# serial.net
KiCad netlist of a schematic drawn in Altium Designer
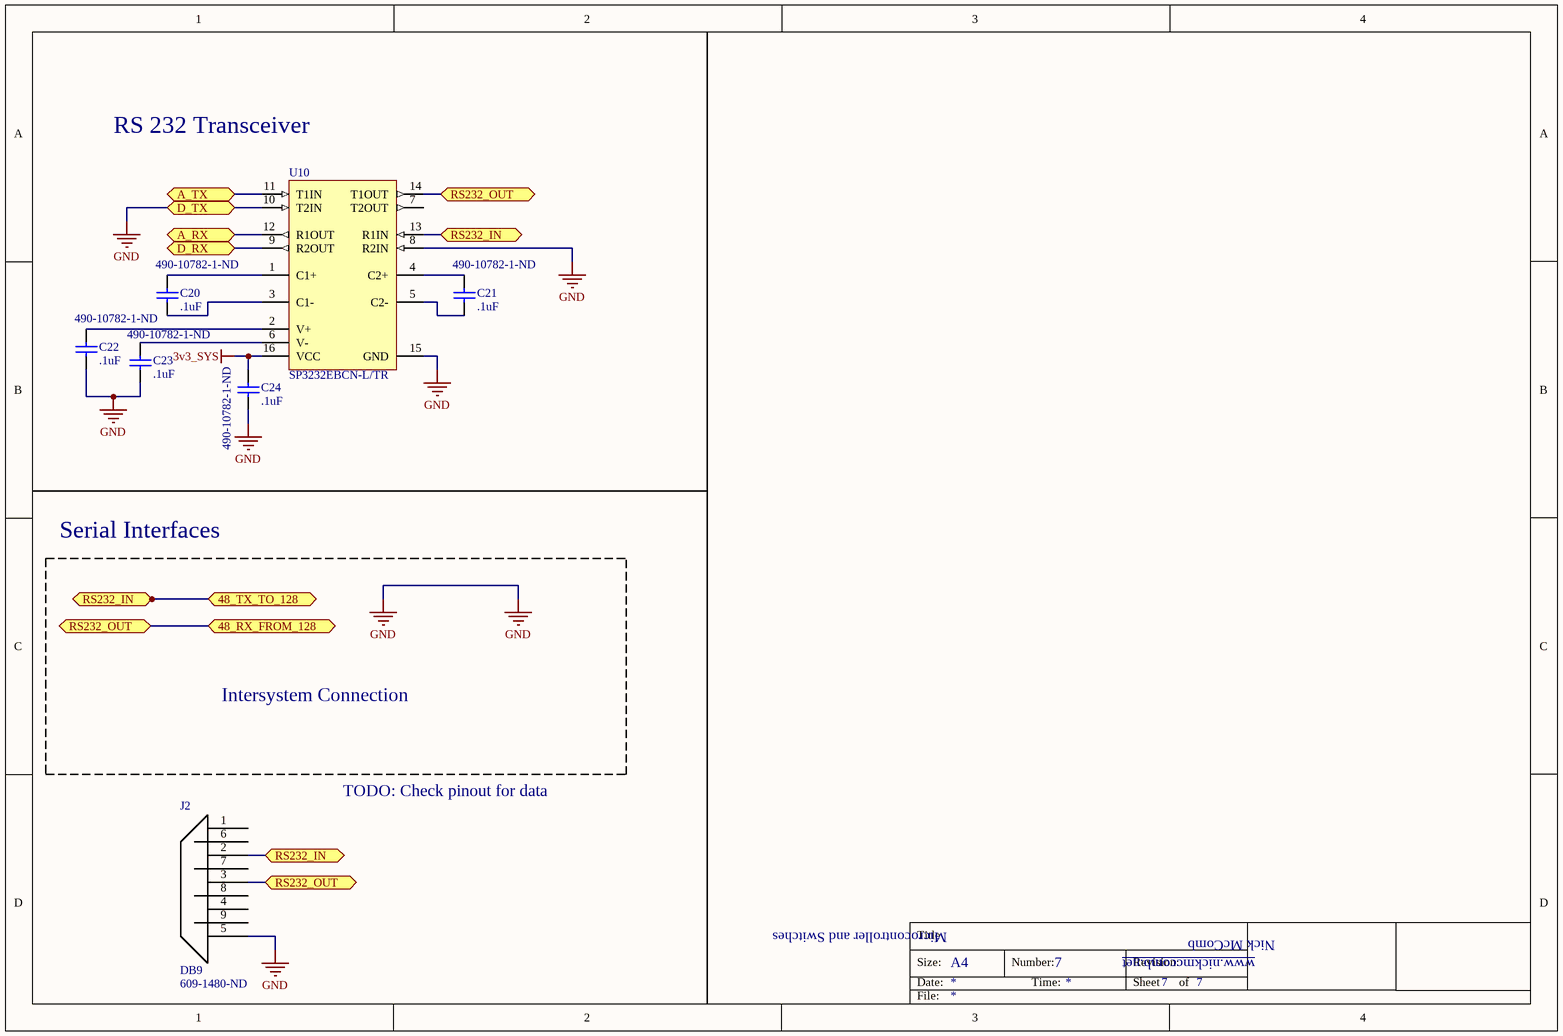
[diagram p0: serial.SchDoc]

(export (version "E")
  (design (tool "Eeschema 10.0.6"))
  (components
    (comp (ref "C20")
      (value ".1uF")
      (footprint "C0805")
      (description "Capacitor")
      (fields
        (field (name "SUPPLIER PART NUMBER 1") "490-10782-1-ND")
        (field (name "MANUFACTURER") "Murata Electronics North America")
        (field (name "MANUFACTURER PART NUMBER") "GRM21BR71H104JA01L")
        (field (name "PUBLISHER") "Altium Limited")
      )
      (libsource (lib "MultiAdapterLib") (part "Cap"))
    )
    (comp (ref "C21")
      (value ".1uF")
      (footprint "C0805")
      (description "Capacitor")
      (fields
        (field (name "SUPPLIER PART NUMBER 1") "490-10782-1-ND")
        (field (name "MANUFACTURER") "Murata Electronics North America")
        (field (name "MANUFACTURER PART NUMBER") "GRM21BR71H104JA01L")
        (field (name "PUBLISHER") "Altium Limited")
      )
      (libsource (lib "MultiAdapterLib") (part "Cap"))
    )
    (comp (ref "C22")
      (value ".1uF")
      (footprint "C0805")
      (description "Capacitor")
      (fields
        (field (name "SUPPLIER PART NUMBER 1") "490-10782-1-ND")
        (field (name "MANUFACTURER") "Murata Electronics North America")
        (field (name "MANUFACTURER PART NUMBER") "GRM21BR71H104JA01L")
        (field (name "PUBLISHER") "Altium Limited")
      )
      (libsource (lib "MultiAdapterLib") (part "Cap"))
    )
    (comp (ref "C23")
      (value ".1uF")
      (footprint "C0805")
      (description "Capacitor")
      (fields
        (field (name "SUPPLIER PART NUMBER 1") "490-10782-1-ND")
        (field (name "MANUFACTURER") "Murata Electronics North America")
        (field (name "MANUFACTURER PART NUMBER") "GRM21BR71H104JA01L")
        (field (name "PUBLISHER") "Altium Limited")
      )
      (libsource (lib "MultiAdapterLib") (part "Cap"))
    )
    (comp (ref "C24")
      (value ".1uF")
      (footprint "C0805")
      (description "Capacitor")
      (fields
        (field (name "SUPPLIER PART NUMBER 1") "490-10782-1-ND")
        (field (name "MANUFACTURER") "Murata Electronics North America")
        (field (name "MANUFACTURER PART NUMBER") "GRM21BR71H104JA01L")
        (field (name "PUBLISHER") "Altium Limited")
      )
      (libsource (lib "MultiAdapterLib") (part "Cap"))
    )
    (comp (ref "J2")
      (value "DB9")
      (footprint "DSUB CONNECTOR")
      (fields
        (field (name "MANUFACTURER") "Amphenol / FCI")
        (field (name "MANUFACTURER PART NUMBER") "D09P33E4GV00LF")
        (field (name "SUPPLIER PART NUMBER 1") "609-1480-ND")
      )
      (libsource (lib "lab2") (part "DB9"))
    )
    (comp (ref "U10")
      (value "SP3232EBCN-L/TR")
      (footprint "EXAR-NSOIC-16_N")
      (fields (field (name "MANUFACTURER") "Exar Corporation"))
      (libsource (lib "Altium Content Vault") (part "EXAR-SP3232EB-16"))
    )
  )
  (nets
    (net (code "1") (name "/48_RX_FROM_128") (class "Default")
      (node (ref "J2") (pin "3") (pintype "passive"))
      (node (ref "U10") (pin "14") (pinfunction "T1OUT_14") (pintype "output"))
    )
    (net (code "3") (name "/A_RX") (class "Default")
      (node (ref "U10") (pin "12") (pinfunction "R1OUT_12") (pintype "output"))
    )
    (net (code "4") (name "/A_TX") (class "Default")
      (node (ref "U10") (pin "11") (pinfunction "T1IN_11") (pintype "input"))
    )
    (net (code "5") (name "/D_RX") (class "Default")
      (node (ref "U10") (pin "9") (pinfunction "R2OUT_9") (pintype "output"))
    )
    (net (code "6") (name "/RS232_IN") (class "Default")
      (node (ref "J2") (pin "2") (pintype "passive"))
      (node (ref "U10") (pin "13") (pinfunction "R1IN_13") (pintype "input"))
    )
    (net (code "7") (name "3v3_SYS") (class "Default")
      (node (ref "C24") (pin "2") (pinfunction "2_2") (pintype "passive"))
      (node (ref "U10") (pin "16") (pinfunction "VCC_16") (pintype "power_in"))
    )
    (net (code "8") (name "GND") (class "Default")
      (node (ref "C22") (pin "1") (pinfunction "1_1") (pintype "passive"))
      (node (ref "C23") (pin "1") (pinfunction "1_1") (pintype "passive"))
      (node (ref "C24") (pin "1") (pinfunction "1_1") (pintype "passive"))
      (node (ref "J2") (pin "5") (pintype "passive"))
      (node (ref "U10") (pin "10") (pinfunction "T2IN_10") (pintype "input"))
      (node (ref "U10") (pin "15") (pinfunction "GND_15") (pintype "power_in"))
      (node (ref "U10") (pin "8") (pinfunction "R2IN_8") (pintype "input"))
    )
    (net (code "9") (name "Net-(U10-C1+)") (class "Default")
      (node (ref "C20") (pin "2") (pinfunction "2_2") (pintype "passive"))
      (node (ref "U10") (pin "1") (pinfunction "C1+_1") (pintype "passive"))
    )
    (net (code "10") (name "Net-(U10-C1-)") (class "Default")
      (node (ref "C20") (pin "1") (pinfunction "1_1") (pintype "passive"))
      (node (ref "U10") (pin "3") (pinfunction "C1-_3") (pintype "passive"))
    )
    (net (code "11") (name "Net-(U10-C2+)") (class "Default")
      (node (ref "C21") (pin "2") (pinfunction "2_2") (pintype "passive"))
      (node (ref "U10") (pin "4") (pinfunction "C2+_4") (pintype "passive"))
    )
    (net (code "12") (name "Net-(U10-C2-)") (class "Default")
      (node (ref "C21") (pin "1") (pinfunction "1_1") (pintype "passive"))
      (node (ref "U10") (pin "5") (pinfunction "C2-_5") (pintype "passive"))
    )
    (net (code "13") (name "Net-(U10-V+)") (class "Default")
      (node (ref "C22") (pin "2") (pinfunction "2_2") (pintype "passive"))
      (node (ref "U10") (pin "2") (pinfunction "V+_2") (pintype "power_in"))
    )
    (net (code "14") (name "Net-(U10-V-)") (class "Default")
      (node (ref "C23") (pin "2") (pinfunction "2_2") (pintype "passive"))
      (node (ref "U10") (pin "6") (pinfunction "V-_6") (pintype "power_in"))
    )
    (net (code "15") (name "unconnected-(J2-Pad1)") (class "Default")
      (node (ref "J2") (pin "1") (pintype "passive"))
    )
    (net (code "16") (name "unconnected-(J2-Pad4)") (class "Default")
      (node (ref "J2") (pin "4") (pintype "passive"))
    )
    (net (code "17") (name "unconnected-(J2-Pad6)") (class "Default")
      (node (ref "J2") (pin "6") (pintype "passive"))
    )
    (net (code "18") (name "unconnected-(J2-Pad7)") (class "Default")
      (node (ref "J2") (pin "7") (pintype "passive"))
    )
    (net (code "19") (name "unconnected-(J2-Pad8)") (class "Default")
      (node (ref "J2") (pin "8") (pintype "passive"))
    )
    (net (code "20") (name "unconnected-(J2-Pad9)") (class "Default")
      (node (ref "J2") (pin "9") (pintype "passive"))
    )
    (net (code "21") (name "unconnected-(U10-T2OUT-Pad7)") (class "Default")
      (node (ref "U10") (pin "7") (pinfunction "T2OUT_7") (pintype "output"))
    )
  )
)
